# MTX_Tap_an_er_V13_Nopoti_2018_11_30.net
KiCad netlist of a schematic drawn in EAGLE
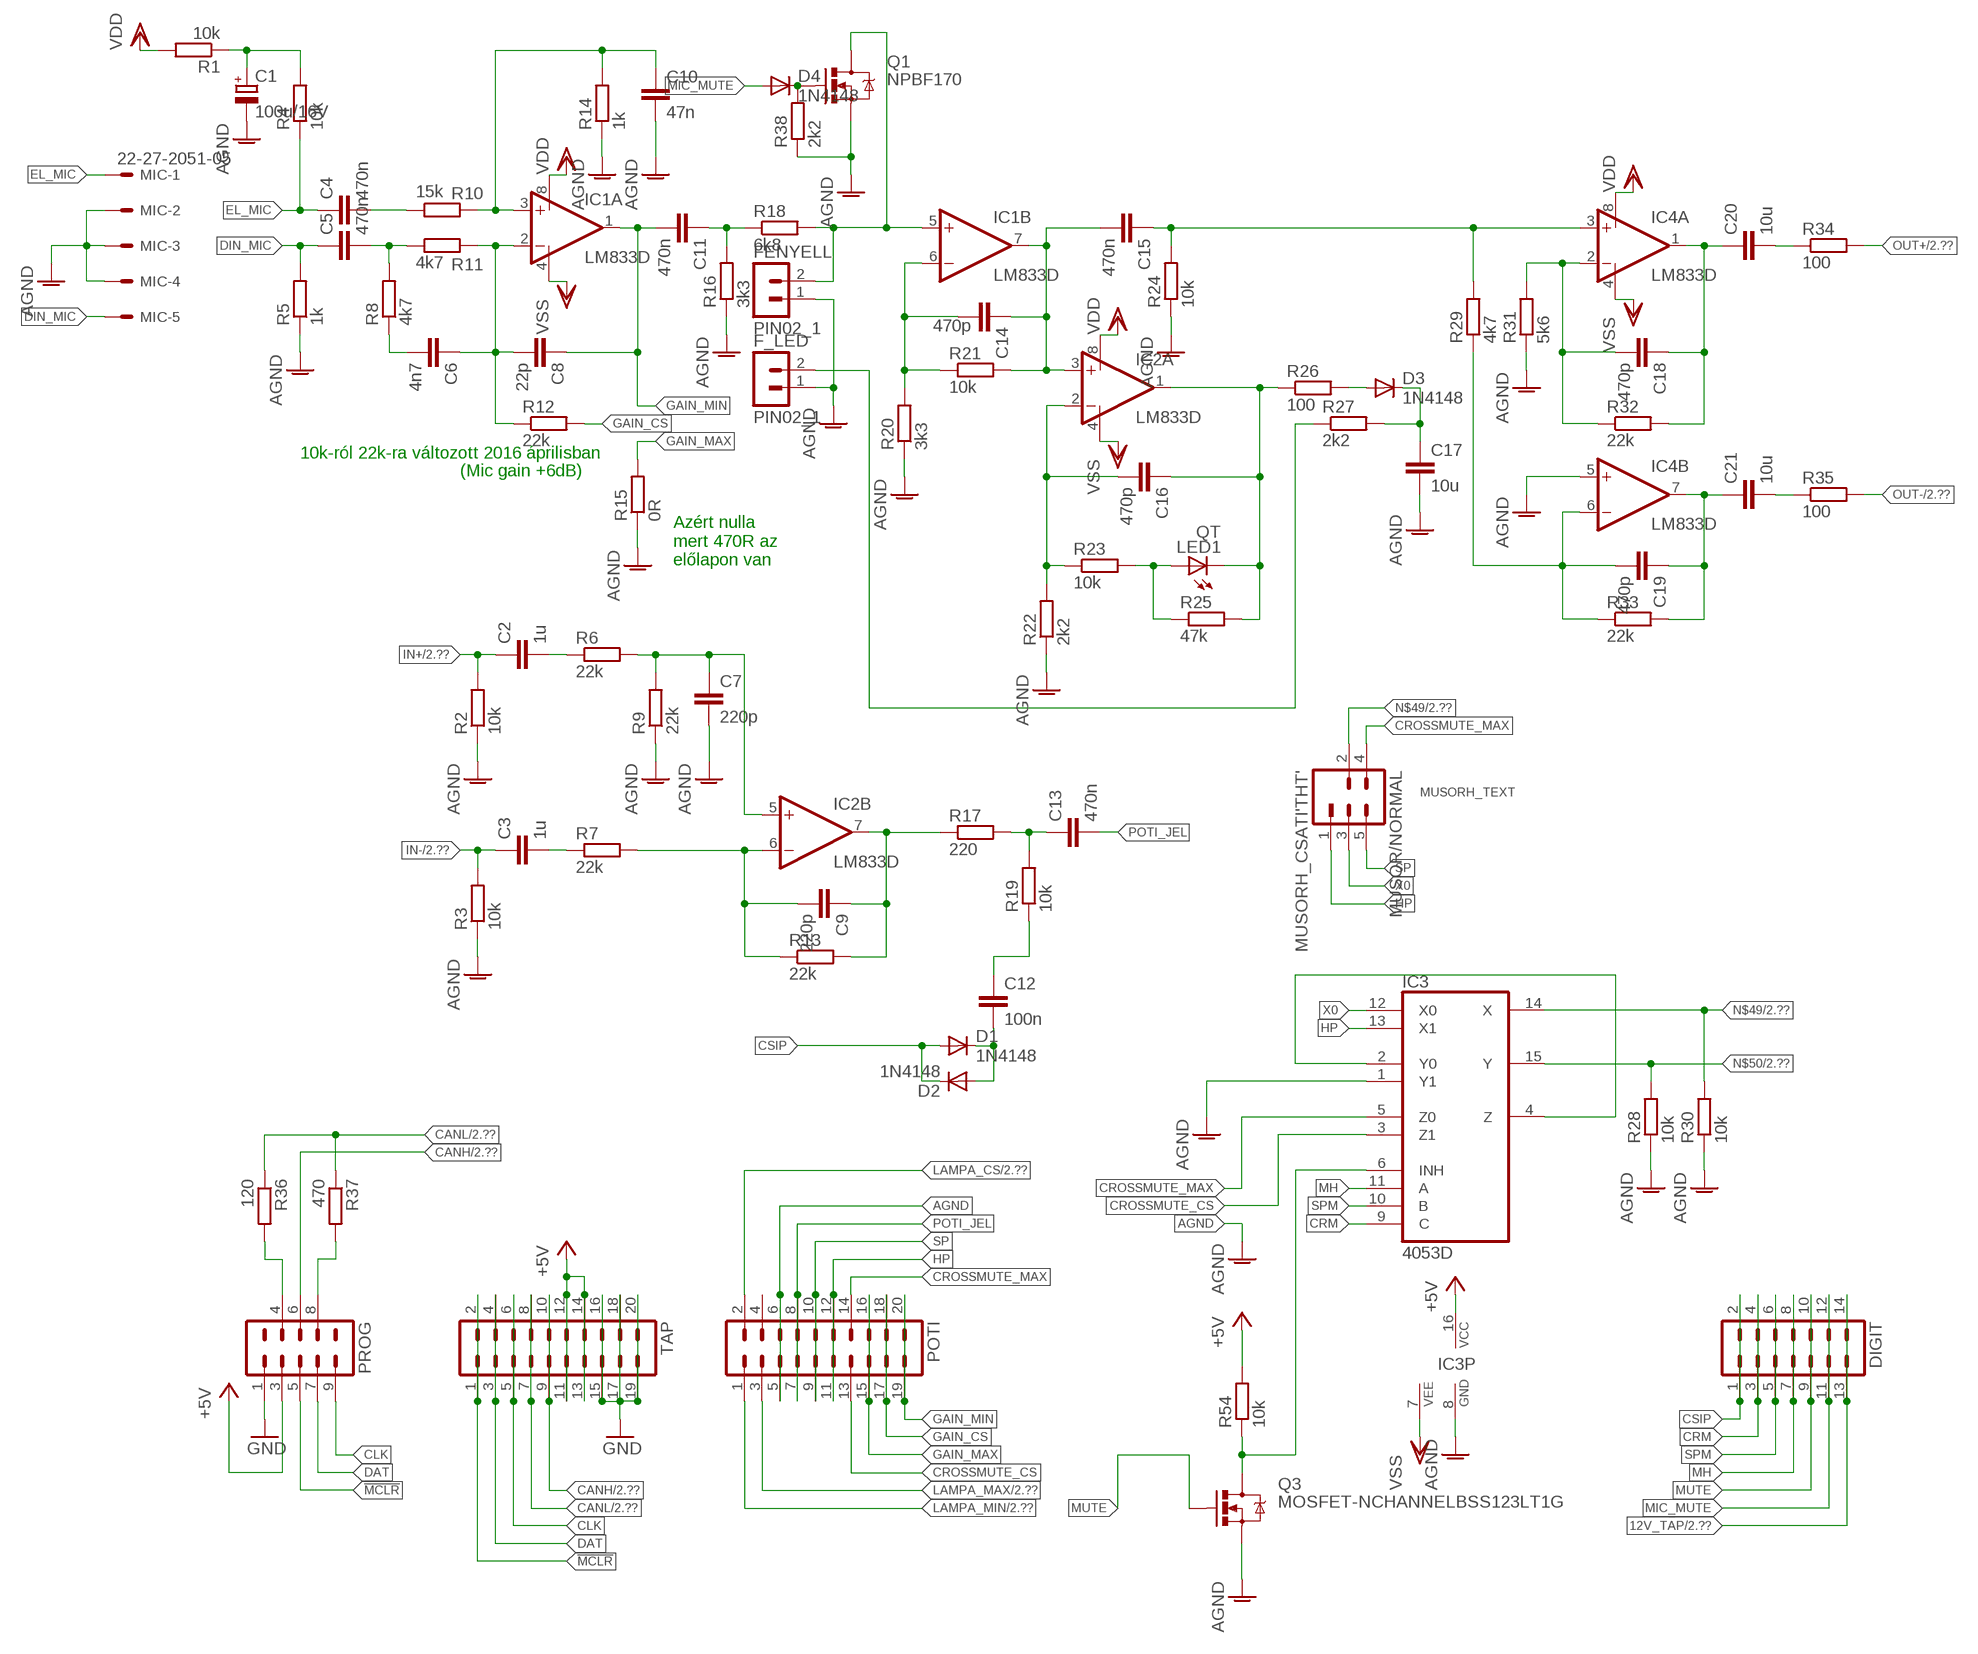
[diagram p0: schematic, sheet 1]
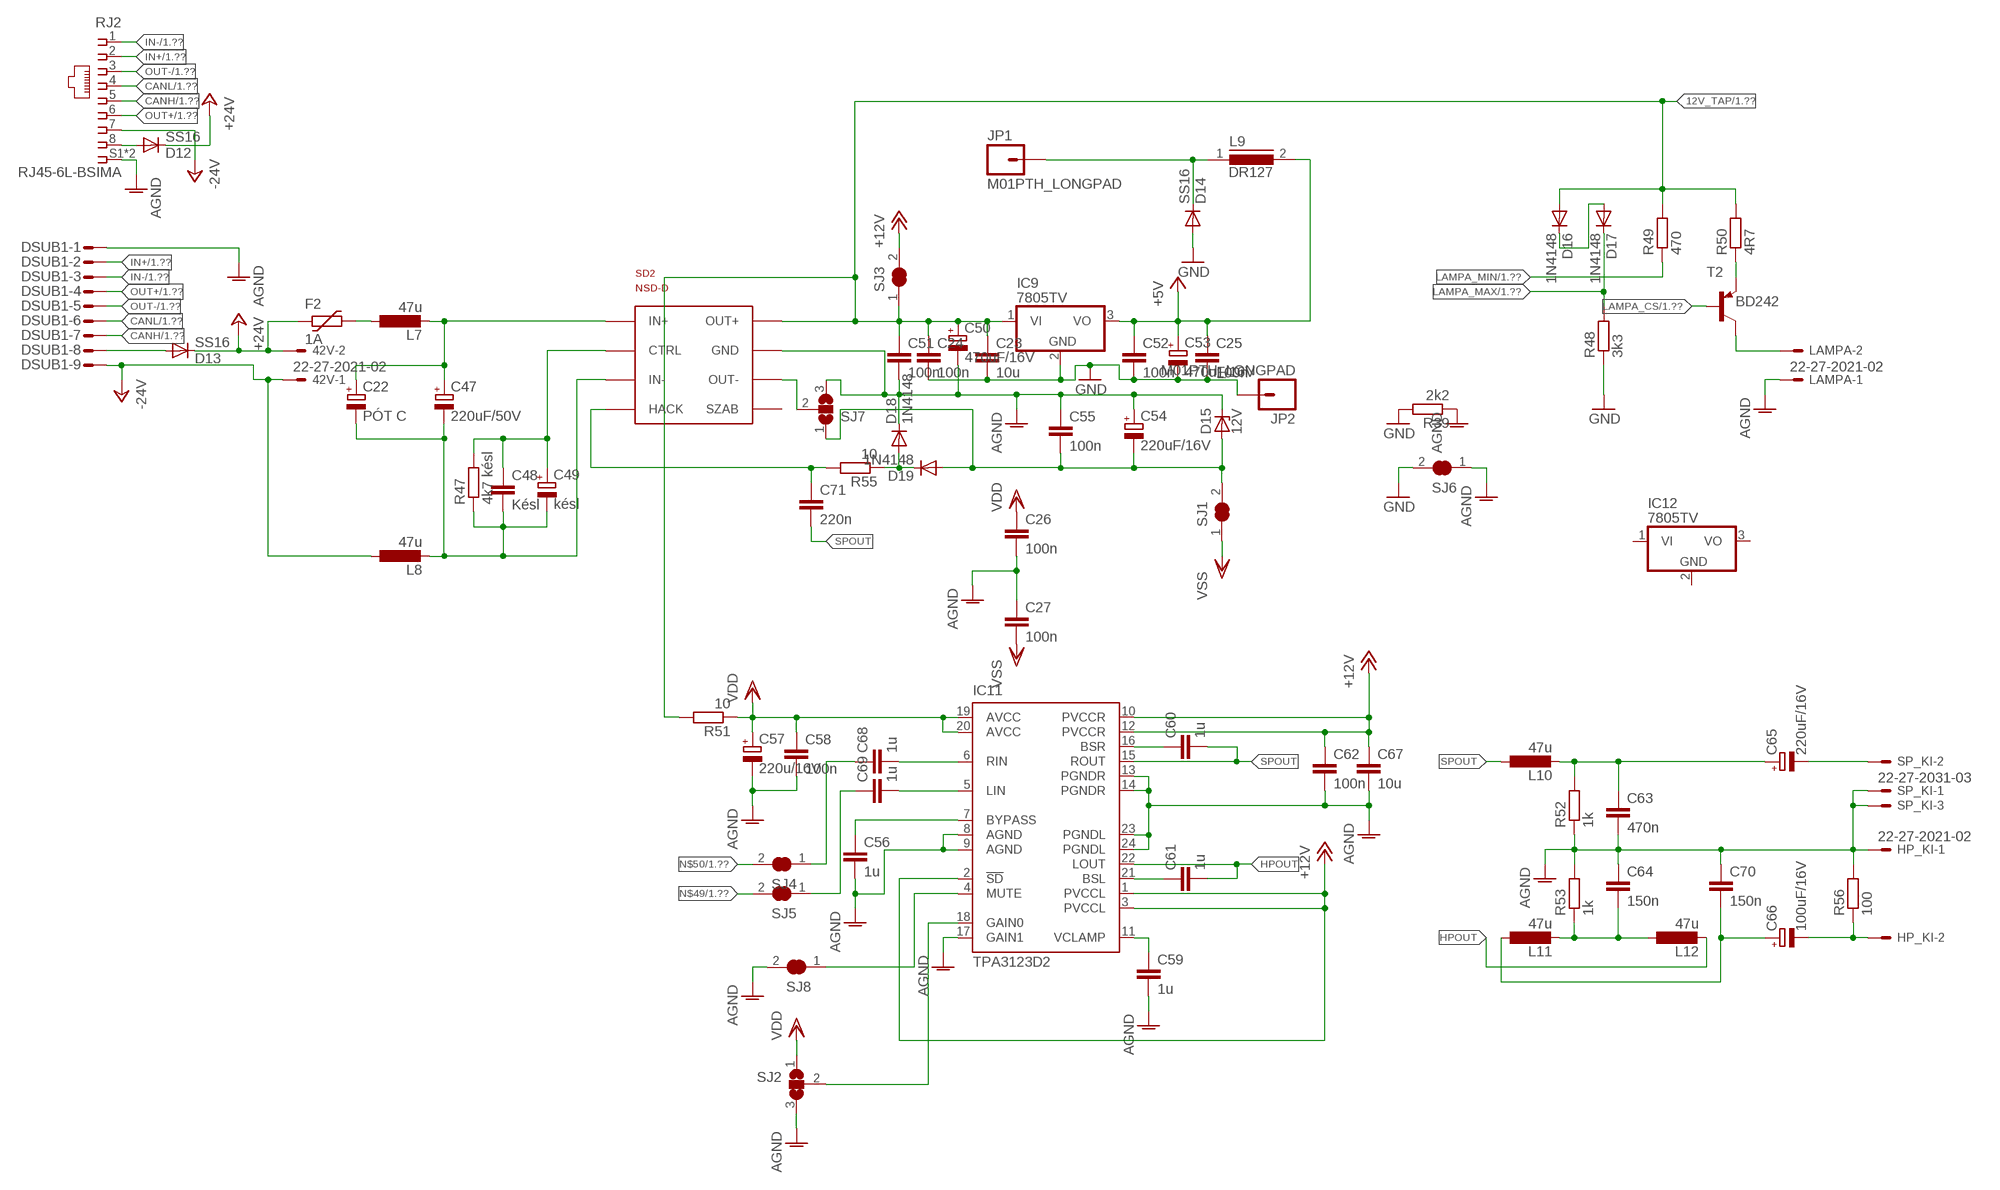
[diagram p1: schematic, sheet 2]

(export (version "E")
  (design (tool "Eeschema 10.0.6"))
  (components
    (comp (ref "42V")
      (value "22-27-2021-02")
      (footprint "eagle-import:6410-02")
      (libsource (lib "eagle-import") (part "22-?-0227-2021"))
    )
    (comp (ref "C22")
      (value "PÓT C")
      (footprint "eagle-import:E3,5-8")
      (libsource (lib "eagle-import") (part "CPOL-EUE3.5-8"))
    )
    (comp (ref "C23")
      (value "10u")
      (footprint "eagle-import:C0805")
      (libsource (lib "eagle-import") (part "C-EUC0805"))
    )
    (comp (ref "C24")
      (value "100n")
      (footprint "eagle-import:C0805")
      (libsource (lib "eagle-import") (part "C-EUC0805"))
    )
    (comp (ref "C25")
      (value "100n")
      (footprint "eagle-import:C0805")
      (libsource (lib "eagle-import") (part "C-EUC0805"))
    )
    (comp (ref "C26")
      (value "100n")
      (footprint "eagle-import:C0805")
      (libsource (lib "eagle-import") (part "C-EUC0805"))
    )
    (comp (ref "C27")
      (value "100n")
      (footprint "eagle-import:C0805")
      (libsource (lib "eagle-import") (part "C-EUC0805"))
    )
    (comp (ref "C47")
      (value "220uF/50V")
      (footprint "eagle-import:E3,5-8")
      (libsource (lib "eagle-import") (part "CPOL-EUE3.5-8"))
    )
    (comp (ref "C48")
      (value "Késl")
      (footprint "eagle-import:C0805")
      (libsource (lib "eagle-import") (part "C-EUC0805"))
    )
    (comp (ref "C49")
      (value "késl")
      (footprint "eagle-import:E2,5-5")
      (libsource (lib "eagle-import") (part "CPOL-EUE2.5-5"))
    )
    (comp (ref "C50")
      (value "470uF/16V")
      (footprint "eagle-import:E3,5-8")
      (libsource (lib "eagle-import") (part "CPOL-EUE3.5-8"))
    )
    (comp (ref "C51")
      (value "100n")
      (footprint "eagle-import:C0805")
      (libsource (lib "eagle-import") (part "C-EUC0805"))
    )
    (comp (ref "C52")
      (value "100n")
      (footprint "eagle-import:C0805")
      (libsource (lib "eagle-import") (part "C-EUC0805"))
    )
    (comp (ref "C53")
      (value "470uF/16V")
      (footprint "eagle-import:E3,5-8")
      (libsource (lib "eagle-import") (part "CPOL-EUE3.5-8"))
    )
    (comp (ref "C54")
      (value "220uF/16V")
      (footprint "eagle-import:E2,5-7")
      (libsource (lib "eagle-import") (part "CPOL-EUE2.5-7"))
    )
    (comp (ref "C55")
      (value "100n")
      (footprint "eagle-import:C0805")
      (libsource (lib "eagle-import") (part "C-EUC0805"))
    )
    (comp (ref "C56")
      (value "1u")
      (footprint "eagle-import:C0805")
      (libsource (lib "eagle-import") (part "C-EUC0805"))
    )
    (comp (ref "C57")
      (value "220u/16V")
      (footprint "eagle-import:E2,5-7")
      (libsource (lib "eagle-import") (part "CPOL-EUE2.5-7"))
    )
    (comp (ref "C58")
      (value "100n")
      (footprint "eagle-import:C0805")
      (libsource (lib "eagle-import") (part "C-EUC0805"))
    )
    (comp (ref "C59")
      (value "1u")
      (footprint "eagle-import:C0805")
      (libsource (lib "eagle-import") (part "C-EUC0805"))
    )
    (comp (ref "C60")
      (value "1u")
      (footprint "eagle-import:C0805")
      (libsource (lib "eagle-import") (part "C-EUC0805"))
    )
    (comp (ref "C61")
      (value "1u")
      (footprint "eagle-import:C0805")
      (libsource (lib "eagle-import") (part "C-EUC0805"))
    )
    (comp (ref "C62")
      (value "100n")
      (footprint "eagle-import:C0805")
      (libsource (lib "eagle-import") (part "C-EUC0805"))
    )
    (comp (ref "C63")
      (value "470n")
      (footprint "eagle-import:C0805")
      (libsource (lib "eagle-import") (part "C-EUC0805"))
    )
    (comp (ref "C64")
      (value "150n")
      (footprint "eagle-import:C0805")
      (libsource (lib "eagle-import") (part "C-EUC0805"))
    )
    (comp (ref "C65")
      (value "220uF/16V")
      (footprint "eagle-import:E2,5-7")
      (libsource (lib "eagle-import") (part "CPOL-EUE2.5-7"))
    )
    (comp (ref "C66")
      (value "100uF/16V")
      (footprint "eagle-import:E2,5-6")
      (libsource (lib "eagle-import") (part "CPOL-EUE2.5-6"))
    )
    (comp (ref "C67")
      (value "10u")
      (footprint "eagle-import:C0805")
      (libsource (lib "eagle-import") (part "C-EUC0805"))
    )
    (comp (ref "C68")
      (value "1u")
      (footprint "eagle-import:C0805")
      (libsource (lib "eagle-import") (part "C-EUC0805"))
    )
    (comp (ref "C69")
      (value "1u")
      (footprint "eagle-import:C0805")
      (libsource (lib "eagle-import") (part "C-EUC0805"))
    )
    (comp (ref "C70")
      (value "150n")
      (footprint "eagle-import:C0805")
      (libsource (lib "eagle-import") (part "C-EUC0805"))
    )
    (comp (ref "C71")
      (value "220n")
      (footprint "eagle-import:C0805")
      (libsource (lib "eagle-import") (part "C-EUC0805"))
    )
    (comp (ref "D12")
      (value "SS16")
      (footprint "eagle-import:DO-214AC")
      (libsource (lib "eagle-import") (part "dp_devices_DIODE-DO-214AC"))
    )
    (comp (ref "D13")
      (value "SS16")
      (footprint "eagle-import:DO-214AC")
      (libsource (lib "eagle-import") (part "dp_devices_DIODE-DO-214AC"))
    )
    (comp (ref "D14")
      (value "SS16")
      (footprint "eagle-import:DO-214AC")
      (libsource (lib "eagle-import") (part "dp_devices_DIODE-DO-214AC"))
    )
    (comp (ref "D15")
      (value "12V")
      (footprint "eagle-import:SOD80C")
      (libsource (lib "eagle-import") (part "ZENER-DIODESOD80C"))
    )
    (comp (ref "D16")
      (value "1N4148")
      (footprint "eagle-import:SOD80C")
      (libsource (lib "eagle-import") (part "DIODE-SOD80C"))
    )
    (comp (ref "D17")
      (value "1N4148")
      (footprint "eagle-import:SOD80C")
      (libsource (lib "eagle-import") (part "DIODE-SOD80C"))
    )
    (comp (ref "D18")
      (value "1N4148")
      (footprint "eagle-import:SOD80C")
      (libsource (lib "eagle-import") (part "DIODE-SOD80C"))
    )
    (comp (ref "D19")
      (value "1N4148")
      (footprint "eagle-import:SOD80C")
      (libsource (lib "eagle-import") (part "DIODE-SOD80C"))
    )
    (comp (ref "DSUB1")
      (value "M09-182S")
      (footprint "eagle-import:182-009-MALE")
      (libsource (lib "eagle-import") (part "M09?S-182"))
    )
    (comp (ref "F2")
      (value "1A")
      (footprint "eagle-import:PTC1812L")
      (libsource (lib "eagle-import") (part "FUSE_PTC-1812"))
    )
    (comp (ref "HP_KI")
      (value "22-27-2021-02")
      (footprint "eagle-import:6410-02")
      (libsource (lib "eagle-import") (part "22-?-0227-2021"))
    )
    (comp (ref "IC9")
      (value "7805TV")
      (footprint "eagle-import:TO220V")
      (libsource (lib "eagle-import") (part "78TV05"))
    )
    (comp (ref "IC11")
      (value "TPA3123D2")
      (footprint "eagle-import:PWP-TSSOP24")
      (fields (field (name "MPN") "TPA3123D2PWP"))
      (libsource (lib "eagle-import") (part "TPA3123D2"))
    )
    (comp (ref "IC12")
      (value "7805TV")
      (footprint "eagle-import:TO220V")
      (libsource (lib "eagle-import") (part "78TV05"))
    )
    (comp (ref "JP1")
      (value "M01PTH_LONGPAD")
      (footprint "eagle-import:1X01_LONGPAD")
      (libsource (lib "eagle-import") (part "M01PTH_LONGPAD"))
    )
    (comp (ref "JP2")
      (value "M01PTH_LONGPAD")
      (footprint "eagle-import:1X01_LONGPAD")
      (libsource (lib "eagle-import") (part "M01PTH_LONGPAD"))
    )
    (comp (ref "L7")
      (value "47u")
      (footprint "eagle-import:PIS2816")
      (libsource (lib "eagle-import") (part "L-EUPIS2816"))
    )
    (comp (ref "L8")
      (value "47u")
      (footprint "eagle-import:PIS2816")
      (libsource (lib "eagle-import") (part "L-EUPIS2816"))
    )
    (comp (ref "L9")
      (value "DR127")
      (footprint "eagle-import:DR127")
      (libsource (lib "eagle-import") (part "DR127"))
    )
    (comp (ref "L10")
      (value "47u")
      (footprint "eagle-import:PIS2816")
      (libsource (lib "eagle-import") (part "L-EUPIS2816"))
    )
    (comp (ref "L11")
      (value "47u")
      (footprint "eagle-import:PIS2816")
      (libsource (lib "eagle-import") (part "L-EUPIS2816"))
    )
    (comp (ref "L12")
      (value "47u")
      (footprint "eagle-import:PIS2816")
      (libsource (lib "eagle-import") (part "L-EUPIS2816"))
    )
    (comp (ref "LAMPA")
      (value "22-27-2021-02")
      (footprint "eagle-import:6410-02")
      (libsource (lib "eagle-import") (part "22-?-0227-2021"))
    )
    (comp (ref "R39")
      (value "2k2")
      (footprint "eagle-import:R0805")
      (libsource (lib "eagle-import") (part "R-EU_R0805"))
    )
    (comp (ref "R47")
      (value "4k7 késl")
      (footprint "eagle-import:R0805")
      (libsource (lib "eagle-import") (part "R-EU_R0805"))
    )
    (comp (ref "R48")
      (value "3k3")
      (footprint "eagle-import:R0805")
      (libsource (lib "eagle-import") (part "R-EU_R0805"))
    )
    (comp (ref "R49")
      (value "470")
      (footprint "eagle-import:R0805")
      (libsource (lib "eagle-import") (part "R-EU_R0805"))
    )
    (comp (ref "R50")
      (value "4R7")
      (footprint "eagle-import:R0805")
      (libsource (lib "eagle-import") (part "R-EU_R0805"))
    )
    (comp (ref "R51")
      (value "10")
      (footprint "eagle-import:R1210")
      (libsource (lib "eagle-import") (part "R-EU_R1210"))
    )
    (comp (ref "R52")
      (value "1k")
      (footprint "eagle-import:R0805")
      (libsource (lib "eagle-import") (part "R-EU_R0805"))
    )
    (comp (ref "R53")
      (value "1k")
      (footprint "eagle-import:R0805")
      (libsource (lib "eagle-import") (part "R-EU_R0805"))
    )
    (comp (ref "R55")
      (value "10")
      (footprint "eagle-import:R0805")
      (libsource (lib "eagle-import") (part "R-EU_R0805"))
    )
    (comp (ref "R56")
      (value "100")
      (footprint "eagle-import:R0805")
      (libsource (lib "eagle-import") (part "R-EU_R0805"))
    )
    (comp (ref "RJ2")
      (value "RJ45-6L-BSIMA")
      (footprint "eagle-import:RJ45")
      (fields (field (name "MPN") "RJ45-6L-B"))
      (libsource (lib "eagle-import") (part "RJ45SIMA-6L-B"))
    )
    (comp (ref "SD2")
      (value "NSD-D")
      (footprint "eagle-import:NSD-D")
      (libsource (lib "eagle-import") (part "NSD-D"))
    )
    (comp (ref "SJ1")
      (value "SOLDERJUMPER_CLOSED")
      (footprint "eagle-import:SOLDERJUMPER_CLOSEDWIRE")
      (libsource (lib "eagle-import") (part "SOLDERJUMPER_CLOSED"))
    )
    (comp (ref "SJ2")
      (value "SJ2WW12")
      (footprint "eagle-import:SJ_2W_12")
      (libsource (lib "eagle-import") (part "SJ2WW12"))
    )
    (comp (ref "SJ3")
      (value "SOLDERJUMPER_CLOSED")
      (footprint "eagle-import:SOLDERJUMPER_CLOSEDWIRE")
      (libsource (lib "eagle-import") (part "SOLDERJUMPER_CLOSED"))
    )
    (comp (ref "SJ4")
      (value "SOLDERJUMPER_CLOSED")
      (footprint "eagle-import:SOLDERJUMPER_CLOSEDWIRE")
      (libsource (lib "eagle-import") (part "SOLDERJUMPER_CLOSED"))
    )
    (comp (ref "SJ5")
      (value "SOLDERJUMPER_CLOSED")
      (footprint "eagle-import:SOLDERJUMPER_CLOSEDWIRE")
      (libsource (lib "eagle-import") (part "SOLDERJUMPER_CLOSED"))
    )
    (comp (ref "SJ6")
      (value "SOLDERJUMPER_CLOSED")
      (footprint "eagle-import:SOLDERJUMPER_CLOSEDWIRE")
      (libsource (lib "eagle-import") (part "SOLDERJUMPER_CLOSED"))
    )
    (comp (ref "SJ7")
      (value "SJ2WW23")
      (footprint "eagle-import:SJ_2W_23")
      (libsource (lib "eagle-import") (part "SJ2WW23"))
    )
    (comp (ref "SJ8")
      (value "SOLDERJUMPER_CLOSED")
      (footprint "eagle-import:SOLDERJUMPER_CLOSEDWIRE")
      (libsource (lib "eagle-import") (part "SOLDERJUMPER_CLOSED"))
    )
    (comp (ref "SP_KI")
      (value "22-27-2031-03")
      (footprint "eagle-import:6410-03")
      (libsource (lib "eagle-import") (part "22-?-0327-2031"))
    )
    (comp (ref "T2")
      (value "BD242")
      (footprint "eagle-import:TO220V")
      (libsource (lib "eagle-import") (part "-PNP-TO220V"))
    )
    (comp (ref "C1")
      (value "100u/16V")
      (footprint "eagle-import:E2,5-5")
      (libsource (lib "eagle-import") (part "CPOL-EUE2.5-5"))
    )
    (comp (ref "C2")
      (value "1u")
      (footprint "eagle-import:C0805")
      (libsource (lib "eagle-import") (part "C-EUC0805"))
    )
    (comp (ref "C3")
      (value "1u")
      (footprint "eagle-import:C0805")
      (libsource (lib "eagle-import") (part "C-EUC0805"))
    )
    (comp (ref "C4")
      (value "470n")
      (footprint "eagle-import:C0805")
      (libsource (lib "eagle-import") (part "C-EUC0805"))
    )
    (comp (ref "C5")
      (value "470n")
      (footprint "eagle-import:C0805")
      (libsource (lib "eagle-import") (part "C-EUC0805"))
    )
    (comp (ref "C6")
      (value "4n7")
      (footprint "eagle-import:C0805")
      (libsource (lib "eagle-import") (part "C-EUC0805"))
    )
    (comp (ref "C7")
      (value "220p")
      (footprint "eagle-import:C0805")
      (libsource (lib "eagle-import") (part "C-EUC0805"))
    )
    (comp (ref "C8")
      (value "22p")
      (footprint "eagle-import:C0805")
      (libsource (lib "eagle-import") (part "C-EUC0805"))
    )
    (comp (ref "C9")
      (value "220p")
      (footprint "eagle-import:C0805")
      (libsource (lib "eagle-import") (part "C-EUC0805"))
    )
    (comp (ref "C10")
      (value "47n")
      (footprint "eagle-import:C0805")
      (libsource (lib "eagle-import") (part "C-EUC0805"))
    )
    (comp (ref "C11")
      (value "470n")
      (footprint "eagle-import:C0805")
      (libsource (lib "eagle-import") (part "C-EUC0805"))
    )
    (comp (ref "C12")
      (value "100n")
      (footprint "eagle-import:C0805")
      (libsource (lib "eagle-import") (part "C-EUC0805"))
    )
    (comp (ref "C13")
      (value "470n")
      (footprint "eagle-import:C0805")
      (libsource (lib "eagle-import") (part "C-EUC0805"))
    )
    (comp (ref "C14")
      (value "470p")
      (footprint "eagle-import:C0805")
      (libsource (lib "eagle-import") (part "C-EUC0805"))
    )
    (comp (ref "C15")
      (value "470n")
      (footprint "eagle-import:C0805")
      (libsource (lib "eagle-import") (part "C-EUC0805"))
    )
    (comp (ref "C16")
      (value "470p")
      (footprint "eagle-import:C0805")
      (libsource (lib "eagle-import") (part "C-EUC0805"))
    )
    (comp (ref "C17")
      (value "10u")
      (footprint "eagle-import:C0805")
      (libsource (lib "eagle-import") (part "C-EUC0805"))
    )
    (comp (ref "C18")
      (value "470p")
      (footprint "eagle-import:C0805")
      (libsource (lib "eagle-import") (part "C-EUC0805"))
    )
    (comp (ref "C19")
      (value "470p")
      (footprint "eagle-import:C0805")
      (libsource (lib "eagle-import") (part "C-EUC0805"))
    )
    (comp (ref "C20")
      (value "10u")
      (footprint "eagle-import:C0805")
      (libsource (lib "eagle-import") (part "C-EUC0805"))
    )
    (comp (ref "C21")
      (value "10u")
      (footprint "eagle-import:C0805")
      (libsource (lib "eagle-import") (part "C-EUC0805"))
    )
    (comp (ref "D1")
      (value "1N4148")
      (footprint "eagle-import:SOD80C")
      (libsource (lib "eagle-import") (part "DIODE-SOD80C"))
    )
    (comp (ref "D2")
      (value "1N4148")
      (footprint "eagle-import:SOD80C")
      (libsource (lib "eagle-import") (part "DIODE-SOD80C"))
    )
    (comp (ref "D3")
      (value "1N4148")
      (footprint "eagle-import:SOD80C")
      (libsource (lib "eagle-import") (part "DIODE-SOD80C"))
    )
    (comp (ref "D4")
      (value "1N4148")
      (footprint "eagle-import:SOD80C")
      (libsource (lib "eagle-import") (part "DIODE-SOD80C"))
    )
    (comp (ref "DIGIT")
      (value "MA07-2")
      (footprint "eagle-import:MA07-2")
      (libsource (lib "eagle-import") (part "MA07-2"))
    )
    (comp (ref "FENYELL")
      (value "PIN02_1")
      (footprint "eagle-import:PIN02_1")
      (libsource (lib "eagle-import") (part "PIN02_1"))
    )
    (comp (ref "F_LED")
      (value "PIN02_1")
      (footprint "eagle-import:PIN02_1")
      (libsource (lib "eagle-import") (part "PIN02_1"))
    )
    (comp (ref "IC1")
      (value "LM833D")
      (footprint "eagle-import:SO08")
      (libsource (lib "eagle-import") (part "LM833D"))
    )
    (comp (ref "IC2")
      (value "LM833D")
      (footprint "eagle-import:SO08")
      (libsource (lib "eagle-import") (part "LM833D"))
    )
    (comp (ref "IC3")
      (value "4053D")
      (footprint "eagle-import:SO16")
      (libsource (lib "eagle-import") (part "4053D"))
    )
    (comp (ref "IC4")
      (value "LM833D")
      (footprint "eagle-import:SO08")
      (libsource (lib "eagle-import") (part "LM833D"))
    )
    (comp (ref "LED1")
      (value "QT")
      (footprint "eagle-import:LED3MM")
      (libsource (lib "eagle-import") (part "LED3MM"))
    )
    (comp (ref "MIC")
      (value "22-27-2051-05")
      (footprint "eagle-import:6410-05")
      (libsource (lib "eagle-import") (part "22-?-0527-2051"))
    )
    (comp (ref "MUSOR/NORMAL")
      (value "MUSORH_CSATI'THT'")
      (footprint "eagle-import:MUSORH_CSATI")
      (libsource (lib "eagle-import") (part "MUSORH_CSATI'THT'"))
    )
    (comp (ref "POTI")
      (value "MA10-2")
      (footprint "eagle-import:MA10-2")
      (libsource (lib "eagle-import") (part "MA10-2"))
    )
    (comp (ref "PROG")
      (value "CN_CANTAN")
      (footprint "eagle-import:CN_CANTAN")
      (libsource (lib "eagle-import") (part "CN_CANTAN"))
    )
    (comp (ref "Q1")
      (value "NPBF170")
      (footprint "eagle-import:SOT23")
      (libsource (lib "eagle-import") (part "MOSFET-NCHANNELBSS138"))
    )
    (comp (ref "Q3")
      (value "MOSFET-NCHANNELBSS123LT1G")
      (footprint "eagle-import:SOT23")
      (libsource (lib "eagle-import") (part "MOSFET-NCHANNELBSS123LT1G"))
    )
    (comp (ref "R1")
      (value "10k")
      (footprint "eagle-import:R0805")
      (libsource (lib "eagle-import") (part "R-EU_R0805"))
    )
    (comp (ref "R2")
      (value "10k")
      (footprint "eagle-import:R0805")
      (libsource (lib "eagle-import") (part "R-EU_R0805"))
    )
    (comp (ref "R3")
      (value "10k")
      (footprint "eagle-import:R0805")
      (libsource (lib "eagle-import") (part "R-EU_R0805"))
    )
    (comp (ref "R4")
      (value "10k")
      (footprint "eagle-import:R0805")
      (libsource (lib "eagle-import") (part "R-EU_R0805"))
    )
    (comp (ref "R5")
      (value "1k")
      (footprint "eagle-import:R0805")
      (libsource (lib "eagle-import") (part "R-EU_R0805"))
    )
    (comp (ref "R6")
      (value "22k")
      (footprint "eagle-import:R0805")
      (libsource (lib "eagle-import") (part "R-EU_R0805"))
    )
    (comp (ref "R7")
      (value "22k")
      (footprint "eagle-import:R0805")
      (libsource (lib "eagle-import") (part "R-EU_R0805"))
    )
    (comp (ref "R8")
      (value "4k7")
      (footprint "eagle-import:R0805")
      (libsource (lib "eagle-import") (part "R-EU_R0805"))
    )
    (comp (ref "R9")
      (value "22k")
      (footprint "eagle-import:R0805")
      (libsource (lib "eagle-import") (part "R-EU_R0805"))
    )
    (comp (ref "R10")
      (value "15k")
      (footprint "eagle-import:R0805")
      (libsource (lib "eagle-import") (part "R-EU_R0805"))
    )
    (comp (ref "R11")
      (value "4k7")
      (footprint "eagle-import:R0805")
      (libsource (lib "eagle-import") (part "R-EU_R0805"))
    )
    (comp (ref "R12")
      (value "22k")
      (footprint "eagle-import:R0805")
      (libsource (lib "eagle-import") (part "R-EU_R0805"))
    )
    (comp (ref "R13")
      (value "22k")
      (footprint "eagle-import:R0805")
      (libsource (lib "eagle-import") (part "R-EU_R0805"))
    )
    (comp (ref "R14")
      (value "1k")
      (footprint "eagle-import:R0805")
      (libsource (lib "eagle-import") (part "R-EU_R0805"))
    )
    (comp (ref "R15")
      (value "0R")
      (footprint "eagle-import:R0805")
      (libsource (lib "eagle-import") (part "R-EU_R0805"))
    )
    (comp (ref "R16")
      (value "3k3")
      (footprint "eagle-import:R0805")
      (libsource (lib "eagle-import") (part "R-EU_R0805"))
    )
    (comp (ref "R17")
      (value "220")
      (footprint "eagle-import:R0805")
      (libsource (lib "eagle-import") (part "R-EU_R0805"))
    )
    (comp (ref "R18")
      (value "6k8")
      (footprint "eagle-import:R0805")
      (libsource (lib "eagle-import") (part "R-EU_R0805"))
    )
    (comp (ref "R19")
      (value "10k")
      (footprint "eagle-import:R0805")
      (libsource (lib "eagle-import") (part "R-EU_R0805"))
    )
    (comp (ref "R20")
      (value "3k3")
      (footprint "eagle-import:R0805")
      (libsource (lib "eagle-import") (part "R-EU_R0805"))
    )
    (comp (ref "R21")
      (value "10k")
      (footprint "eagle-import:R0805")
      (libsource (lib "eagle-import") (part "R-EU_R0805"))
    )
    (comp (ref "R22")
      (value "2k2")
      (footprint "eagle-import:R0805")
      (libsource (lib "eagle-import") (part "R-EU_R0805"))
    )
    (comp (ref "R23")
      (value "10k")
      (footprint "eagle-import:R0805")
      (libsource (lib "eagle-import") (part "R-EU_R0805"))
    )
    (comp (ref "R24")
      (value "10k")
      (footprint "eagle-import:R0805")
      (libsource (lib "eagle-import") (part "R-EU_R0805"))
    )
    (comp (ref "R25")
      (value "47k")
      (footprint "eagle-import:R0805")
      (libsource (lib "eagle-import") (part "R-EU_R0805"))
    )
    (comp (ref "R26")
      (value "100")
      (footprint "eagle-import:R0805")
      (libsource (lib "eagle-import") (part "R-EU_R0805"))
    )
    (comp (ref "R27")
      (value "2k2")
      (footprint "eagle-import:R0805")
      (libsource (lib "eagle-import") (part "R-EU_R0805"))
    )
    (comp (ref "R28")
      (value "10k")
      (footprint "eagle-import:R0805")
      (libsource (lib "eagle-import") (part "R-EU_R0805"))
    )
    (comp (ref "R29")
      (value "4k7")
      (footprint "eagle-import:R0805")
      (libsource (lib "eagle-import") (part "R-EU_R0805"))
    )
    (comp (ref "R30")
      (value "10k")
      (footprint "eagle-import:R0805")
      (libsource (lib "eagle-import") (part "R-EU_R0805"))
    )
    (comp (ref "R31")
      (value "5k6")
      (footprint "eagle-import:R0805")
      (libsource (lib "eagle-import") (part "R-EU_R0805"))
    )
    (comp (ref "R32")
      (value "22k")
      (footprint "eagle-import:R0805")
      (libsource (lib "eagle-import") (part "R-EU_R0805"))
    )
    (comp (ref "R33")
      (value "22k")
      (footprint "eagle-import:R0805")
      (libsource (lib "eagle-import") (part "R-EU_R0805"))
    )
    (comp (ref "R34")
      (value "100")
      (footprint "eagle-import:R0805")
      (libsource (lib "eagle-import") (part "R-EU_R0805"))
    )
    (comp (ref "R35")
      (value "100")
      (footprint "eagle-import:R0805")
      (libsource (lib "eagle-import") (part "R-EU_R0805"))
    )
    (comp (ref "R36")
      (value "120")
      (footprint "eagle-import:R0805")
      (libsource (lib "eagle-import") (part "R-EU_R0805"))
    )
    (comp (ref "R37")
      (value "470")
      (footprint "eagle-import:R0805")
      (libsource (lib "eagle-import") (part "R-EU_R0805"))
    )
    (comp (ref "R38")
      (value "2k2")
      (footprint "eagle-import:R0805")
      (libsource (lib "eagle-import") (part "R-EU_R0805"))
    )
    (comp (ref "R54")
      (value "10k")
      (footprint "eagle-import:R0805")
      (libsource (lib "eagle-import") (part "R-EU_R0805"))
    )
    (comp (ref "TAP")
      (value "MA10-2")
      (footprint "eagle-import:MA10-2")
      (libsource (lib "eagle-import") (part "MA10-2"))
    )
    (comp (ref "U$1")
      (value "MUSORH_TEXT")
      (footprint "eagle-import:MUSORH_TEXT")
      (libsource (lib "eagle-import") (part "MUSORH_TEXT"))
    )
  )
  (nets
    (net (code "1") (name "+5V") (class "Default")
      (node (ref "C25") (pin "1") (pinfunction "1_1") (pintype "passive"))
      (node (ref "C52") (pin "1") (pinfunction "1_1") (pintype "passive"))
      (node (ref "C53") (pin "+") (pinfunction "+_+") (pintype "passive"))
      (node (ref "IC3") (pin "16") (pinfunction "VCC_16") (pintype "power_in"))
      (node (ref "IC9") (pin "3") (pinfunction "VO_3") (pintype "passive"))
      (node (ref "L9") (pin "2") (pinfunction "2_2") (pintype "passive"))
      (node (ref "PROG") (pin "3") (pinfunction "3_3") (pintype "passive"))
      (node (ref "R54") (pin "2") (pinfunction "2_2") (pintype "passive"))
      (node (ref "TAP") (pin "11") (pinfunction "11_11") (pintype "passive"))
      (node (ref "TAP") (pin "12") (pinfunction "12_12") (pintype "passive"))
      (node (ref "TAP") (pin "13") (pinfunction "13_13") (pintype "passive"))
      (node (ref "TAP") (pin "14") (pinfunction "14_14") (pintype "passive"))
    )
    (net (code "2") (name "+12V") (class "Default")
      (node (ref "C62") (pin "1") (pinfunction "1_1") (pintype "passive"))
      (node (ref "C67") (pin "1") (pinfunction "1_1") (pintype "passive"))
      (node (ref "IC11") (pin "1") (pinfunction "PVCCL_1") (pintype "input"))
      (node (ref "IC11") (pin "10") (pinfunction "PVCCR_10") (pintype "input"))
      (node (ref "IC11") (pin "12") (pinfunction "PVCCR_12") (pintype "input"))
      (node (ref "IC11") (pin "2") (pinfunction "~{SD}_2") (pintype "input"))
      (node (ref "IC11") (pin "3") (pinfunction "PVCCL_3") (pintype "input"))
      (node (ref "SJ3") (pin "2") (pinfunction "2_2") (pintype "passive"))
    )
    (net (code "3") (name "+24V") (class "Default")
      (node (ref "42V") (pin "2") (pinfunction "S_2") (pintype "passive"))
      (node (ref "D12") (pin "1") (pinfunction "C_1") (pintype "passive"))
      (node (ref "D13") (pin "1") (pinfunction "C_1") (pintype "passive"))
      (node (ref "F2") (pin "1") (pinfunction "1_1") (pintype "passive"))
    )
    (net (code "4") (name "-24V") (class "Default")
      (node (ref "42V") (pin "1") (pinfunction "S_1") (pintype "passive"))
      (node (ref "DSUB1") (pin "9") (pinfunction "M_9") (pintype "passive"))
      (node (ref "L8") (pin "1") (pinfunction "1_1") (pintype "passive"))
      (node (ref "RJ2") (pin "7") (pinfunction "7_7") (pintype "passive"))
    )
    (net (code "5") (name "12V_TAP") (class "Default")
      (node (ref "C23") (pin "1") (pinfunction "1_1") (pintype "passive"))
      (node (ref "C24") (pin "1") (pinfunction "1_1") (pintype "passive"))
      (node (ref "C50") (pin "+") (pinfunction "+_+") (pintype "passive"))
      (node (ref "C51") (pin "1") (pinfunction "1_1") (pintype "passive"))
      (node (ref "D16") (pin "A") (pinfunction "A_A") (pintype "passive"))
      (node (ref "DIGIT") (pin "13") (pinfunction "13_13") (pintype "passive"))
      (node (ref "DIGIT") (pin "14") (pinfunction "14_14") (pintype "passive"))
      (node (ref "IC9") (pin "1") (pinfunction "VI_1") (pintype "input"))
      (node (ref "R49") (pin "2") (pinfunction "2_2") (pintype "passive"))
      (node (ref "R50") (pin "2") (pinfunction "2_2") (pintype "passive"))
      (node (ref "R51") (pin "2") (pinfunction "2_2") (pintype "passive"))
      (node (ref "SD2") (pin "OUT+") (pinfunction "OUT+_OUT+") (pintype "bidirectional"))
      (node (ref "SJ3") (pin "1") (pinfunction "1_1") (pintype "passive"))
    )
    (net (code "6") (name "AGND") (class "Default")
      (node (ref "C1") (pin "-") (pinfunction "-_-") (pintype "passive"))
      (node (ref "C10") (pin "2") (pinfunction "2_2") (pintype "passive"))
      (node (ref "C17") (pin "2") (pinfunction "2_2") (pintype "passive"))
      (node (ref "C26") (pin "2") (pinfunction "2_2") (pintype "passive"))
      (node (ref "C27") (pin "1") (pinfunction "1_1") (pintype "passive"))
      (node (ref "C50") (pin "-") (pinfunction "-_-") (pintype "passive"))
      (node (ref "C51") (pin "2") (pinfunction "2_2") (pintype "passive"))
      (node (ref "C54") (pin "+") (pinfunction "+_+") (pintype "passive"))
      (node (ref "C55") (pin "1") (pinfunction "1_1") (pintype "passive"))
      (node (ref "C56") (pin "2") (pinfunction "2_2") (pintype "passive"))
      (node (ref "C57") (pin "-") (pinfunction "-_-") (pintype "passive"))
      (node (ref "C58") (pin "2") (pinfunction "2_2") (pintype "passive"))
      (node (ref "C59") (pin "2") (pinfunction "2_2") (pintype "passive"))
      (node (ref "C62") (pin "2") (pinfunction "2_2") (pintype "passive"))
      (node (ref "C63") (pin "2") (pinfunction "2_2") (pintype "passive"))
      (node (ref "C64") (pin "1") (pinfunction "1_1") (pintype "passive"))
      (node (ref "C67") (pin "2") (pinfunction "2_2") (pintype "passive"))
      (node (ref "C7") (pin "2") (pinfunction "2_2") (pintype "passive"))
      (node (ref "C70") (pin "1") (pinfunction "1_1") (pintype "passive"))
      (node (ref "D15") (pin "C") (pinfunction "C_C") (pintype "passive"))
      (node (ref "D18") (pin "C") (pinfunction "C_C") (pintype "passive"))
      (node (ref "DSUB1") (pin "1") (pinfunction "M_1") (pintype "passive"))
      (node (ref "FENYELL") (pin "1") (pinfunction "1_1") (pintype "passive"))
      (node (ref "F_LED") (pin "1") (pinfunction "1_1") (pintype "passive"))
      (node (ref "HP_KI") (pin "1") (pinfunction "S_1") (pintype "passive"))
      (node (ref "IC11") (pin "13") (pinfunction "PGNDR_13") (pintype "input"))
      (node (ref "IC11") (pin "14") (pinfunction "PGNDR_14") (pintype "input"))
      (node (ref "IC11") (pin "17") (pinfunction "GAIN1_17") (pintype "input"))
      (node (ref "IC11") (pin "23") (pinfunction "PGNDL_23") (pintype "input"))
      (node (ref "IC11") (pin "24") (pinfunction "PGNDL_24") (pintype "input"))
      (node (ref "IC11") (pin "8") (pinfunction "AGND_8") (pintype "input"))
      (node (ref "IC11") (pin "9") (pinfunction "AGND_9") (pintype "input"))
      (node (ref "IC3") (pin "1") (pinfunction "Y1_1") (pintype "bidirectional"))
      (node (ref "IC3") (pin "8") (pinfunction "GND_8") (pintype "power_in"))
      (node (ref "IC4") (pin "5") (pinfunction "+IN_5") (pintype "input"))
      (node (ref "LAMPA") (pin "1") (pinfunction "S_1") (pintype "passive"))
      (node (ref "MIC") (pin "2") (pinfunction "S_2") (pintype "passive"))
      (node (ref "MIC") (pin "3") (pinfunction "S_3") (pintype "passive"))
      (node (ref "MIC") (pin "4") (pinfunction "S_4") (pintype "passive"))
      (node (ref "POTI") (pin "5") (pinfunction "5_5") (pintype "passive"))
      (node (ref "POTI") (pin "6") (pinfunction "6_6") (pintype "passive"))
      (node (ref "Q1") (pin "2") (pinfunction "S_2") (pintype "passive"))
      (node (ref "Q3") (pin "2") (pinfunction "S_2") (pintype "passive"))
      (node (ref "R14") (pin "1") (pinfunction "1_1") (pintype "passive"))
      (node (ref "R15") (pin "1") (pinfunction "1_1") (pintype "passive"))
      (node (ref "R16") (pin "1") (pinfunction "1_1") (pintype "passive"))
      (node (ref "R2") (pin "1") (pinfunction "1_1") (pintype "passive"))
      (node (ref "R20") (pin "1") (pinfunction "1_1") (pintype "passive"))
      (node (ref "R22") (pin "1") (pinfunction "1_1") (pintype "passive"))
      (node (ref "R24") (pin "1") (pinfunction "1_1") (pintype "passive"))
      (node (ref "R28") (pin "1") (pinfunction "1_1") (pintype "passive"))
      (node (ref "R3") (pin "1") (pinfunction "1_1") (pintype "passive"))
      (node (ref "R30") (pin "1") (pinfunction "1_1") (pintype "passive"))
      (node (ref "R31") (pin "1") (pinfunction "1_1") (pintype "passive"))
      (node (ref "R38") (pin "1") (pinfunction "1_1") (pintype "passive"))
      (node (ref "R39") (pin "1") (pinfunction "1_1") (pintype "passive"))
      (node (ref "R5") (pin "1") (pinfunction "1_1") (pintype "passive"))
      (node (ref "R52") (pin "1") (pinfunction "1_1") (pintype "passive"))
      (node (ref "R53") (pin "2") (pinfunction "2_2") (pintype "passive"))
      (node (ref "R56") (pin "2") (pinfunction "2_2") (pintype "passive"))
      (node (ref "R9") (pin "1") (pinfunction "1_1") (pintype "passive"))
      (node (ref "RJ2") (pin "S1") (pinfunction "S_S1") (pintype "passive"))
      (node (ref "RJ2") (pin "S2") (pinfunction "S_S2") (pintype "passive"))
      (node (ref "SD2") (pin "COMMON") (pinfunction "GND_COMMON") (pintype "bidirectional"))
      (node (ref "SJ2") (pin "3") (pinfunction "3_3") (pintype "passive"))
      (node (ref "SJ6") (pin "1") (pinfunction "1_1") (pintype "passive"))
      (node (ref "SJ7") (pin "3") (pinfunction "3_3") (pintype "passive"))
      (node (ref "SJ8") (pin "2") (pinfunction "2_2") (pintype "passive"))
      (node (ref "SP_KI") (pin "1") (pinfunction "S_1") (pintype "passive"))
      (node (ref "SP_KI") (pin "3") (pinfunction "S_3") (pintype "passive"))
    )
    (net (code "7") (name "CANH") (class "Default")
      (node (ref "DSUB1") (pin "7") (pinfunction "M_7") (pintype "passive"))
      (node (ref "PROG") (pin "6") (pinfunction "6_6") (pintype "passive"))
      (node (ref "RJ2") (pin "5") (pinfunction "5_5") (pintype "passive"))
      (node (ref "TAP") (pin "10") (pinfunction "10_10") (pintype "passive"))
      (node (ref "TAP") (pin "9") (pinfunction "9_9") (pintype "passive"))
    )
    (net (code "8") (name "CANL") (class "Default")
      (node (ref "DSUB1") (pin "6") (pinfunction "M_6") (pintype "passive"))
      (node (ref "R36") (pin "1") (pinfunction "1_1") (pintype "passive"))
      (node (ref "R37") (pin "1") (pinfunction "1_1") (pintype "passive"))
      (node (ref "RJ2") (pin "4") (pinfunction "4_4") (pintype "passive"))
      (node (ref "TAP") (pin "7") (pinfunction "7_7") (pintype "passive"))
      (node (ref "TAP") (pin "8") (pinfunction "8_8") (pintype "passive"))
    )
    (net (code "9") (name "CLK") (class "Default")
      (node (ref "PROG") (pin "9") (pinfunction "9_9") (pintype "passive"))
      (node (ref "TAP") (pin "5") (pinfunction "5_5") (pintype "passive"))
      (node (ref "TAP") (pin "6") (pinfunction "6_6") (pintype "passive"))
    )
    (net (code "10") (name "CRM") (class "Default")
      (node (ref "DIGIT") (pin "3") (pinfunction "3_3") (pintype "passive"))
      (node (ref "DIGIT") (pin "4") (pinfunction "4_4") (pintype "passive"))
      (node (ref "IC3") (pin "9") (pinfunction "C_9") (pintype "input"))
    )
    (net (code "11") (name "CROSSMUTE_CS") (class "Default")
      (node (ref "IC3") (pin "3") (pinfunction "Z1_3") (pintype "bidirectional"))
      (node (ref "POTI") (pin "13") (pinfunction "13_13") (pintype "passive"))
    )
    (net (code "12") (name "CROSSMUTE_MAX") (class "Default")
      (node (ref "IC3") (pin "5") (pinfunction "Z0_5") (pintype "bidirectional"))
      (node (ref "MUSOR/NORMAL") (pin "4") (pinfunction "4_4") (pintype "passive"))
      (node (ref "POTI") (pin "14") (pinfunction "14_14") (pintype "passive"))
    )
    (net (code "13") (name "CSIP") (class "Default")
      (node (ref "D1") (pin "A") (pinfunction "A_A") (pintype "passive"))
      (node (ref "D2") (pin "C") (pinfunction "C_C") (pintype "passive"))
      (node (ref "DIGIT") (pin "1") (pinfunction "1_1") (pintype "passive"))
      (node (ref "DIGIT") (pin "2") (pinfunction "2_2") (pintype "passive"))
    )
    (net (code "14") (name "DAT") (class "Default")
      (node (ref "PROG") (pin "7") (pinfunction "7_7") (pintype "passive"))
      (node (ref "TAP") (pin "3") (pinfunction "3_3") (pintype "passive"))
      (node (ref "TAP") (pin "4") (pinfunction "4_4") (pintype "passive"))
    )
    (net (code "15") (name "DIN_MIC") (class "Default")
      (node (ref "C5") (pin "1") (pinfunction "1_1") (pintype "passive"))
      (node (ref "MIC") (pin "5") (pinfunction "S_5") (pintype "passive"))
      (node (ref "R5") (pin "2") (pinfunction "2_2") (pintype "passive"))
    )
    (net (code "16") (name "EL_MIC") (class "Default")
      (node (ref "C4") (pin "1") (pinfunction "1_1") (pintype "passive"))
      (node (ref "MIC") (pin "1") (pinfunction "S_1") (pintype "passive"))
      (node (ref "R4") (pin "1") (pinfunction "1_1") (pintype "passive"))
    )
    (net (code "17") (name "GAIN_CS") (class "Default")
      (node (ref "POTI") (pin "17") (pinfunction "17_17") (pintype "passive"))
      (node (ref "POTI") (pin "18") (pinfunction "18_18") (pintype "passive"))
      (node (ref "R12") (pin "2") (pinfunction "2_2") (pintype "passive"))
    )
    (net (code "18") (name "GAIN_MAX") (class "Default")
      (node (ref "POTI") (pin "15") (pinfunction "15_15") (pintype "passive"))
      (node (ref "POTI") (pin "16") (pinfunction "16_16") (pintype "passive"))
      (node (ref "R15") (pin "2") (pinfunction "2_2") (pintype "passive"))
    )
    (net (code "19") (name "GAIN_MIN") (class "Default")
      (node (ref "C11") (pin "2") (pinfunction "2_2") (pintype "passive"))
      (node (ref "C8") (pin "1") (pinfunction "1_1") (pintype "passive"))
      (node (ref "IC1") (pin "1") (pinfunction "OUT_1") (pintype "output"))
      (node (ref "POTI") (pin "19") (pinfunction "19_19") (pintype "passive"))
      (node (ref "POTI") (pin "20") (pinfunction "20_20") (pintype "passive"))
    )
    (net (code "20") (name "GND") (class "Default")
      (node (ref "C23") (pin "2") (pinfunction "2_2") (pintype "passive"))
      (node (ref "C24") (pin "2") (pinfunction "2_2") (pintype "passive"))
      (node (ref "C25") (pin "2") (pinfunction "2_2") (pintype "passive"))
      (node (ref "C52") (pin "2") (pinfunction "2_2") (pintype "passive"))
      (node (ref "C53") (pin "-") (pinfunction "-_-") (pintype "passive"))
      (node (ref "D14") (pin "2") (pinfunction "A_2") (pintype "passive"))
      (node (ref "IC9") (pin "2") (pinfunction "GND_2") (pintype "passive"))
      (node (ref "JP2") (pin "1") (pinfunction "1_1") (pintype "passive"))
      (node (ref "PROG") (pin "1") (pinfunction "1_1") (pintype "passive"))
      (node (ref "R39") (pin "2") (pinfunction "2_2") (pintype "passive"))
      (node (ref "R48") (pin "1") (pinfunction "1_1") (pintype "passive"))
      (node (ref "SJ6") (pin "2") (pinfunction "2_2") (pintype "passive"))
      (node (ref "TAP") (pin "15") (pinfunction "15_15") (pintype "passive"))
      (node (ref "TAP") (pin "16") (pinfunction "16_16") (pintype "passive"))
      (node (ref "TAP") (pin "17") (pinfunction "17_17") (pintype "passive"))
      (node (ref "TAP") (pin "18") (pinfunction "18_18") (pintype "passive"))
      (node (ref "TAP") (pin "19") (pinfunction "19_19") (pintype "passive"))
      (node (ref "TAP") (pin "20") (pinfunction "20_20") (pintype "passive"))
    )
    (net (code "21") (name "HP") (class "Default")
      (node (ref "IC3") (pin "13") (pinfunction "X1_13") (pintype "bidirectional"))
      (node (ref "MUSOR/NORMAL") (pin "1") (pinfunction "1_1") (pintype "passive"))
      (node (ref "POTI") (pin "11") (pinfunction "11_11") (pintype "passive"))
      (node (ref "POTI") (pin "12") (pinfunction "12_12") (pintype "passive"))
    )
    (net (code "22") (name "HPOUT") (class "Default")
      (node (ref "C61") (pin "2") (pinfunction "2_2") (pintype "passive"))
      (node (ref "IC11") (pin "22") (pinfunction "LOUT_22") (pintype "output"))
      (node (ref "L12") (pin "2") (pinfunction "2_2") (pintype "passive"))
    )
    (net (code "23") (name "IN+") (class "Default")
      (node (ref "C2") (pin "1") (pinfunction "1_1") (pintype "passive"))
      (node (ref "DSUB1") (pin "2") (pinfunction "M_2") (pintype "passive"))
      (node (ref "R2") (pin "2") (pinfunction "2_2") (pintype "passive"))
      (node (ref "RJ2") (pin "2") (pinfunction "2_2") (pintype "passive"))
    )
    (net (code "24") (name "IN-") (class "Default")
      (node (ref "C3") (pin "1") (pinfunction "1_1") (pintype "passive"))
      (node (ref "DSUB1") (pin "3") (pinfunction "M_3") (pintype "passive"))
      (node (ref "R3") (pin "2") (pinfunction "2_2") (pintype "passive"))
      (node (ref "RJ2") (pin "1") (pinfunction "1_1") (pintype "passive"))
    )
    (net (code "25") (name "LAMPA_CS") (class "Default")
      (node (ref "POTI") (pin "2") (pinfunction "2_2") (pintype "passive"))
      (node (ref "T2") (pin "1") (pinfunction "B_1") (pintype "passive"))
    )
    (net (code "26") (name "LAMPA_MAX") (class "Default")
      (node (ref "D17") (pin "C") (pinfunction "C_C") (pintype "passive"))
      (node (ref "POTI") (pin "3") (pinfunction "3_3") (pintype "passive"))
      (node (ref "R48") (pin "2") (pinfunction "2_2") (pintype "passive"))
    )
    (net (code "27") (name "LAMPA_MIN") (class "Default")
      (node (ref "POTI") (pin "1") (pinfunction "1_1") (pintype "passive"))
      (node (ref "R49") (pin "1") (pinfunction "1_1") (pintype "passive"))
    )
    (net (code "28") (name "MH") (class "Default")
      (node (ref "DIGIT") (pin "7") (pinfunction "7_7") (pintype "passive"))
      (node (ref "DIGIT") (pin "8") (pinfunction "8_8") (pintype "passive"))
      (node (ref "IC3") (pin "11") (pinfunction "A_11") (pintype "input"))
    )
    (net (code "29") (name "MIC_MUTE") (class "Default")
      (node (ref "D4") (pin "A") (pinfunction "A_A") (pintype "passive"))
      (node (ref "DIGIT") (pin "11") (pinfunction "11_11") (pintype "passive"))
      (node (ref "DIGIT") (pin "12") (pinfunction "12_12") (pintype "passive"))
    )
    (net (code "30") (name "MUTE") (class "Default")
      (node (ref "DIGIT") (pin "10") (pinfunction "10_10") (pintype "passive"))
      (node (ref "DIGIT") (pin "9") (pinfunction "9_9") (pintype "passive"))
      (node (ref "Q3") (pin "1") (pinfunction "G_1") (pintype "passive"))
    )
    (net (code "31") (name "N$49") (class "Default")
      (node (ref "IC3") (pin "14") (pinfunction "X_14") (pintype "bidirectional"))
      (node (ref "MUSOR/NORMAL") (pin "2") (pinfunction "2_2") (pintype "passive"))
      (node (ref "R30") (pin "2") (pinfunction "2_2") (pintype "passive"))
      (node (ref "SJ5") (pin "2") (pinfunction "2_2") (pintype "passive"))
    )
    (net (code "32") (name "N$50") (class "Default")
      (node (ref "IC3") (pin "15") (pinfunction "Y_15") (pintype "bidirectional"))
      (node (ref "R28") (pin "2") (pinfunction "2_2") (pintype "passive"))
      (node (ref "SJ4") (pin "2") (pinfunction "2_2") (pintype "passive"))
    )
    (net (code "33") (name "Net-(C1-Pad+)") (class "Default")
      (node (ref "C1") (pin "+") (pinfunction "+_+") (pintype "passive"))
      (node (ref "R1") (pin "1") (pinfunction "1_1") (pintype "passive"))
      (node (ref "R4") (pin "2") (pinfunction "2_2") (pintype "passive"))
    )
    (net (code "34") (name "Net-(C2-Pad2)") (class "Default")
      (node (ref "C2") (pin "2") (pinfunction "2_2") (pintype "passive"))
      (node (ref "R6") (pin "1") (pinfunction "1_1") (pintype "passive"))
    )
    (net (code "35") (name "Net-(C3-Pad2)") (class "Default")
      (node (ref "C3") (pin "2") (pinfunction "2_2") (pintype "passive"))
      (node (ref "R7") (pin "1") (pinfunction "1_1") (pintype "passive"))
    )
    (net (code "36") (name "Net-(C4-Pad2)") (class "Default")
      (node (ref "C4") (pin "2") (pinfunction "2_2") (pintype "passive"))
      (node (ref "R10") (pin "1") (pinfunction "1_1") (pintype "passive"))
    )
    (net (code "37") (name "Net-(C5-Pad2)") (class "Default")
      (node (ref "C5") (pin "2") (pinfunction "2_2") (pintype "passive"))
      (node (ref "R11") (pin "1") (pinfunction "1_1") (pintype "passive"))
      (node (ref "R8") (pin "2") (pinfunction "2_2") (pintype "passive"))
    )
    (net (code "38") (name "Net-(C6-Pad2)") (class "Default")
      (node (ref "C6") (pin "2") (pinfunction "2_2") (pintype "passive"))
      (node (ref "R8") (pin "1") (pinfunction "1_1") (pintype "passive"))
    )
    (net (code "39") (name "Net-(C11-Pad1)") (class "Default")
      (node (ref "C11") (pin "1") (pinfunction "1_1") (pintype "passive"))
      (node (ref "R16") (pin "2") (pinfunction "2_2") (pintype "passive"))
      (node (ref "R18") (pin "1") (pinfunction "1_1") (pintype "passive"))
    )
    (net (code "40") (name "Net-(C12-Pad1)") (class "Default")
      (node (ref "C12") (pin "1") (pinfunction "1_1") (pintype "passive"))
      (node (ref "R19") (pin "1") (pinfunction "1_1") (pintype "passive"))
    )
    (net (code "41") (name "Net-(C12-Pad2)") (class "Default")
      (node (ref "C12") (pin "2") (pinfunction "2_2") (pintype "passive"))
      (node (ref "D1") (pin "C") (pinfunction "C_C") (pintype "passive"))
      (node (ref "D2") (pin "A") (pinfunction "A_A") (pintype "passive"))
    )
    (net (code "42") (name "Net-(C13-Pad1)") (class "Default")
      (node (ref "C13") (pin "1") (pinfunction "1_1") (pintype "passive"))
      (node (ref "R17") (pin "2") (pinfunction "2_2") (pintype "passive"))
      (node (ref "R19") (pin "2") (pinfunction "2_2") (pintype "passive"))
    )
    (net (code "43") (name "Net-(C17-Pad1)") (class "Default")
      (node (ref "C17") (pin "1") (pinfunction "1_1") (pintype "passive"))
      (node (ref "D3") (pin "C") (pinfunction "C_C") (pintype "passive"))
      (node (ref "R27") (pin "2") (pinfunction "2_2") (pintype "passive"))
    )
    (net (code "44") (name "Net-(C20-Pad2)") (class "Default")
      (node (ref "C20") (pin "2") (pinfunction "2_2") (pintype "passive"))
      (node (ref "R34") (pin "1") (pinfunction "1_1") (pintype "passive"))
    )
    (net (code "45") (name "Net-(C21-Pad2)") (class "Default")
      (node (ref "C21") (pin "2") (pinfunction "2_2") (pintype "passive"))
      (node (ref "R35") (pin "1") (pinfunction "1_1") (pintype "passive"))
    )
    (net (code "46") (name "Net-(C54-Pad-)") (class "Default")
      (node (ref "C54") (pin "-") (pinfunction "-_-") (pintype "passive"))
      (node (ref "C55") (pin "2") (pinfunction "2_2") (pintype "passive"))
      (node (ref "D15") (pin "A") (pinfunction "A_A") (pintype "passive"))
      (node (ref "D19") (pin "A") (pinfunction "A_A") (pintype "passive"))
      (node (ref "SJ1") (pin "2") (pinfunction "2_2") (pintype "passive"))
      (node (ref "SJ7") (pin "1") (pinfunction "1_1") (pintype "passive"))
    )
    (net (code "47") (name "Net-(C63-Pad1)") (class "Default")
      (node (ref "C63") (pin "1") (pinfunction "1_1") (pintype "passive"))
      (node (ref "C65") (pin "+") (pinfunction "+_+") (pintype "passive"))
      (node (ref "L10") (pin "2") (pinfunction "2_2") (pintype "passive"))
      (node (ref "R52") (pin "2") (pinfunction "2_2") (pintype "passive"))
    )
    (net (code "48") (name "Net-(C64-Pad2)") (class "Default")
      (node (ref "C64") (pin "2") (pinfunction "2_2") (pintype "passive"))
      (node (ref "L11") (pin "2") (pinfunction "2_2") (pintype "passive"))
      (node (ref "L12") (pin "1") (pinfunction "1_1") (pintype "passive"))
      (node (ref "R53") (pin "1") (pinfunction "1_1") (pintype "passive"))
    )
    (net (code "49") (name "Net-(C66-Pad+)") (class "Default")
      (node (ref "C66") (pin "+") (pinfunction "+_+") (pintype "passive"))
      (node (ref "C70") (pin "2") (pinfunction "2_2") (pintype "passive"))
      (node (ref "L11") (pin "1") (pinfunction "1_1") (pintype "passive"))
    )
    (net (code "50") (name "Net-(C68-Pad1)") (class "Default")
      (node (ref "C68") (pin "1") (pinfunction "1_1") (pintype "passive"))
      (node (ref "SJ4") (pin "1") (pinfunction "1_1") (pintype "passive"))
    )
    (net (code "51") (name "Net-(C69-Pad1)") (class "Default")
      (node (ref "C69") (pin "1") (pinfunction "1_1") (pintype "passive"))
      (node (ref "SJ5") (pin "1") (pinfunction "1_1") (pintype "passive"))
    )
    (net (code "52") (name "Net-(C71-Pad1)") (class "Default")
      (node (ref "C71") (pin "1") (pinfunction "1_1") (pintype "passive"))
      (node (ref "R55") (pin "2") (pinfunction "2_2") (pintype "passive"))
      (node (ref "SD2") (pin "HACK") (pinfunction "HACK_HACK") (pintype "bidirectional"))
    )
    (net (code "53") (name "Net-(D3-PadA)") (class "Default")
      (node (ref "D3") (pin "A") (pinfunction "A_A") (pintype "passive"))
      (node (ref "R26") (pin "2") (pinfunction "2_2") (pintype "passive"))
    )
    (net (code "54") (name "Net-(D12-A)") (class "Default")
      (node (ref "D12") (pin "2") (pinfunction "A_2") (pintype "passive"))
      (node (ref "RJ2") (pin "8") (pinfunction "8_8") (pintype "passive"))
    )
    (net (code "55") (name "Net-(D13-A)") (class "Default")
      (node (ref "D13") (pin "2") (pinfunction "A_2") (pintype "passive"))
      (node (ref "DSUB1") (pin "8") (pinfunction "M_8") (pintype "passive"))
    )
    (net (code "56") (name "Net-(D14-C)") (class "Default")
      (node (ref "D14") (pin "1") (pinfunction "C_1") (pintype "passive"))
      (node (ref "JP1") (pin "1") (pinfunction "1_1") (pintype "passive"))
      (node (ref "L9") (pin "1") (pinfunction "1_1") (pintype "passive"))
    )
    (net (code "57") (name "Net-(D16-PadC)") (class "Default")
      (node (ref "D16") (pin "C") (pinfunction "C_C") (pintype "passive"))
      (node (ref "D17") (pin "A") (pinfunction "A_A") (pintype "passive"))
    )
    (net (code "58") (name "Net-(D18-PadA)") (class "Default")
      (node (ref "D18") (pin "A") (pinfunction "A_A") (pintype "passive"))
      (node (ref "D19") (pin "C") (pinfunction "C_C") (pintype "passive"))
      (node (ref "R55") (pin "1") (pinfunction "1_1") (pintype "passive"))
    )
    (net (code "59") (name "Net-(F2-Pad2)") (class "Default")
      (node (ref "F2") (pin "2") (pinfunction "2_2") (pintype "passive"))
      (node (ref "L7") (pin "1") (pinfunction "1_1") (pintype "passive"))
    )
    (net (code "60") (name "Net-(F_LED-Pad2)") (class "Default")
      (node (ref "F_LED") (pin "2") (pinfunction "2_2") (pintype "passive"))
      (node (ref "R27") (pin "1") (pinfunction "1_1") (pintype "passive"))
    )
    (net (code "61") (name "Net-(HP_KIB-S)") (class "Default")
      (node (ref "C66") (pin "-") (pinfunction "-_-") (pintype "passive"))
      (node (ref "HP_KI") (pin "2") (pinfunction "S_2") (pintype "passive"))
      (node (ref "R56") (pin "1") (pinfunction "1_1") (pintype "passive"))
    )
    (net (code "62") (name "Net-(IC1A-+IN)") (class "Default")
      (node (ref "C10") (pin "1") (pinfunction "1_1") (pintype "passive"))
      (node (ref "IC1") (pin "3") (pinfunction "+IN_3") (pintype "input"))
      (node (ref "R10") (pin "2") (pinfunction "2_2") (pintype "passive"))
      (node (ref "R14") (pin "2") (pinfunction "2_2") (pintype "passive"))
    )
    (net (code "63") (name "Net-(IC1A--IN)") (class "Default")
      (node (ref "C6") (pin "1") (pinfunction "1_1") (pintype "passive"))
      (node (ref "C8") (pin "2") (pinfunction "2_2") (pintype "passive"))
      (node (ref "IC1") (pin "2") (pinfunction "-IN_2") (pintype "input"))
      (node (ref "R11") (pin "2") (pinfunction "2_2") (pintype "passive"))
      (node (ref "R12") (pin "1") (pinfunction "1_1") (pintype "passive"))
    )
    (net (code "64") (name "Net-(IC1B-+IN)") (class "Default")
      (node (ref "FENYELL") (pin "2") (pinfunction "2_2") (pintype "passive"))
      (node (ref "IC1") (pin "5") (pinfunction "+IN_5") (pintype "input"))
      (node (ref "Q1") (pin "3") (pinfunction "D_3") (pintype "passive"))
      (node (ref "R18") (pin "2") (pinfunction "2_2") (pintype "passive"))
    )
    (net (code "65") (name "Net-(IC1B--IN)") (class "Default")
      (node (ref "C14") (pin "2") (pinfunction "2_2") (pintype "passive"))
      (node (ref "IC1") (pin "6") (pinfunction "-IN_6") (pintype "input"))
      (node (ref "R20") (pin "2") (pinfunction "2_2") (pintype "passive"))
      (node (ref "R21") (pin "1") (pinfunction "1_1") (pintype "passive"))
    )
    (net (code "66") (name "Net-(IC1B-OUT)") (class "Default")
      (node (ref "C14") (pin "1") (pinfunction "1_1") (pintype "passive"))
      (node (ref "C15") (pin "2") (pinfunction "2_2") (pintype "passive"))
      (node (ref "IC1") (pin "7") (pinfunction "OUT_7") (pintype "output"))
      (node (ref "IC2") (pin "3") (pinfunction "+IN_3") (pintype "input"))
      (node (ref "R21") (pin "2") (pinfunction "2_2") (pintype "passive"))
    )
    (net (code "67") (name "Net-(IC2A--IN)") (class "Default")
      (node (ref "C16") (pin "2") (pinfunction "2_2") (pintype "passive"))
      (node (ref "IC2") (pin "2") (pinfunction "-IN_2") (pintype "input"))
      (node (ref "R22") (pin "2") (pinfunction "2_2") (pintype "passive"))
      (node (ref "R23") (pin "1") (pinfunction "1_1") (pintype "passive"))
    )
    (net (code "68") (name "Net-(IC2A-OUT)") (class "Default")
      (node (ref "C16") (pin "1") (pinfunction "1_1") (pintype "passive"))
      (node (ref "IC2") (pin "1") (pinfunction "OUT_1") (pintype "output"))
      (node (ref "LED1") (pin "K") (pinfunction "C_K") (pintype "passive"))
      (node (ref "R25") (pin "2") (pinfunction "2_2") (pintype "passive"))
      (node (ref "R26") (pin "1") (pinfunction "1_1") (pintype "passive"))
    )
    (net (code "69") (name "Net-(IC2B-+IN)") (class "Default")
      (node (ref "C7") (pin "1") (pinfunction "1_1") (pintype "passive"))
      (node (ref "IC2") (pin "5") (pinfunction "+IN_5") (pintype "input"))
      (node (ref "R6") (pin "2") (pinfunction "2_2") (pintype "passive"))
      (node (ref "R9") (pin "2") (pinfunction "2_2") (pintype "passive"))
    )
    (net (code "70") (name "Net-(IC2B--IN)") (class "Default")
      (node (ref "C9") (pin "2") (pinfunction "2_2") (pintype "passive"))
      (node (ref "IC2") (pin "6") (pinfunction "-IN_6") (pintype "input"))
      (node (ref "R13") (pin "1") (pinfunction "1_1") (pintype "passive"))
      (node (ref "R7") (pin "2") (pinfunction "2_2") (pintype "passive"))
    )
    (net (code "71") (name "Net-(IC2B-OUT)") (class "Default")
      (node (ref "C9") (pin "1") (pinfunction "1_1") (pintype "passive"))
      (node (ref "IC2") (pin "7") (pinfunction "OUT_7") (pintype "output"))
      (node (ref "R13") (pin "2") (pinfunction "2_2") (pintype "passive"))
      (node (ref "R17") (pin "1") (pinfunction "1_1") (pintype "passive"))
    )
    (net (code "72") (name "Net-(IC3A-INH)") (class "Default")
      (node (ref "IC3") (pin "6") (pinfunction "INH_6") (pintype "input"))
      (node (ref "Q3") (pin "3") (pinfunction "D_3") (pintype "passive"))
      (node (ref "R54") (pin "1") (pinfunction "1_1") (pintype "passive"))
    )
    (net (code "73") (name "Net-(IC3A-Y0)") (class "Default")
      (node (ref "IC3") (pin "2") (pinfunction "Y0_2") (pintype "bidirectional"))
      (node (ref "IC3") (pin "4") (pinfunction "Z_4") (pintype "bidirectional"))
    )
    (net (code "74") (name "Net-(IC4A-+IN)") (class "Default")
      (node (ref "C15") (pin "1") (pinfunction "1_1") (pintype "passive"))
      (node (ref "IC4") (pin "3") (pinfunction "+IN_3") (pintype "input"))
      (node (ref "R24") (pin "2") (pinfunction "2_2") (pintype "passive"))
      (node (ref "R29") (pin "2") (pinfunction "2_2") (pintype "passive"))
    )
    (net (code "75") (name "Net-(IC4A--IN)") (class "Default")
      (node (ref "C18") (pin "2") (pinfunction "2_2") (pintype "passive"))
      (node (ref "IC4") (pin "2") (pinfunction "-IN_2") (pintype "input"))
      (node (ref "R31") (pin "2") (pinfunction "2_2") (pintype "passive"))
      (node (ref "R32") (pin "1") (pinfunction "1_1") (pintype "passive"))
    )
    (net (code "76") (name "Net-(IC4A-OUT)") (class "Default")
      (node (ref "C18") (pin "1") (pinfunction "1_1") (pintype "passive"))
      (node (ref "C20") (pin "1") (pinfunction "1_1") (pintype "passive"))
      (node (ref "IC4") (pin "1") (pinfunction "OUT_1") (pintype "output"))
      (node (ref "R32") (pin "2") (pinfunction "2_2") (pintype "passive"))
    )
    (net (code "77") (name "Net-(IC4B--IN)") (class "Default")
      (node (ref "C19") (pin "2") (pinfunction "2_2") (pintype "passive"))
      (node (ref "IC4") (pin "6") (pinfunction "-IN_6") (pintype "input"))
      (node (ref "R29") (pin "1") (pinfunction "1_1") (pintype "passive"))
      (node (ref "R33") (pin "1") (pinfunction "1_1") (pintype "passive"))
    )
    (net (code "78") (name "Net-(IC4B-OUT)") (class "Default")
      (node (ref "C19") (pin "1") (pinfunction "1_1") (pintype "passive"))
      (node (ref "C21") (pin "1") (pinfunction "1_1") (pintype "passive"))
      (node (ref "IC4") (pin "7") (pinfunction "OUT_7") (pintype "output"))
      (node (ref "R33") (pin "2") (pinfunction "2_2") (pintype "passive"))
    )
    (net (code "79") (name "Net-(IC11-BSL)") (class "Default")
      (node (ref "C61") (pin "1") (pinfunction "1_1") (pintype "passive"))
      (node (ref "IC11") (pin "21") (pinfunction "BSL_21") (pintype "passive"))
    )
    (net (code "80") (name "Net-(IC11-BSR)") (class "Default")
      (node (ref "C60") (pin "1") (pinfunction "1_1") (pintype "passive"))
      (node (ref "IC11") (pin "16") (pinfunction "BSR_16") (pintype "passive"))
    )
    (net (code "81") (name "Net-(IC11-BYPASS)") (class "Default")
      (node (ref "C56") (pin "1") (pinfunction "1_1") (pintype "passive"))
      (node (ref "IC11") (pin "7") (pinfunction "BYPASS_7") (pintype "input"))
    )
    (net (code "82") (name "Net-(IC11-GAIN0)") (class "Default")
      (node (ref "IC11") (pin "18") (pinfunction "GAIN0_18") (pintype "input"))
      (node (ref "SJ2") (pin "2") (pinfunction "2_2") (pintype "passive"))
    )
    (net (code "83") (name "Net-(IC11-LIN)") (class "Default")
      (node (ref "C69") (pin "2") (pinfunction "2_2") (pintype "passive"))
      (node (ref "IC11") (pin "5") (pinfunction "LIN_5") (pintype "input"))
    )
    (net (code "84") (name "Net-(IC11-MUTE)") (class "Default")
      (node (ref "IC11") (pin "4") (pinfunction "MUTE_4") (pintype "input"))
      (node (ref "SJ8") (pin "1") (pinfunction "1_1") (pintype "passive"))
    )
    (net (code "85") (name "Net-(IC11-RIN)") (class "Default")
      (node (ref "C68") (pin "2") (pinfunction "2_2") (pintype "passive"))
      (node (ref "IC11") (pin "6") (pinfunction "RIN_6") (pintype "input"))
    )
    (net (code "86") (name "Net-(IC11-VCLAMP)") (class "Default")
      (node (ref "C59") (pin "1") (pinfunction "1_1") (pintype "passive"))
      (node (ref "IC11") (pin "11") (pinfunction "VCLAMP_11") (pintype "input"))
    )
    (net (code "87") (name "Net-(LAMPAB-S)") (class "Default")
      (node (ref "LAMPA") (pin "2") (pinfunction "S_2") (pintype "passive"))
      (node (ref "T2") (pin "2") (pinfunction "C_2") (pintype "passive"))
    )
    (net (code "88") (name "Net-(LED1-PadA)") (class "Default")
      (node (ref "LED1") (pin "A") (pinfunction "A_A") (pintype "passive"))
      (node (ref "R23") (pin "2") (pinfunction "2_2") (pintype "passive"))
      (node (ref "R25") (pin "1") (pinfunction "1_1") (pintype "passive"))
    )
    (net (code "89") (name "Net-(PROG-Pad4)") (class "Default")
      (node (ref "PROG") (pin "4") (pinfunction "4_4") (pintype "passive"))
      (node (ref "R36") (pin "2") (pinfunction "2_2") (pintype "passive"))
    )
    (net (code "90") (name "Net-(PROG-Pad8)") (class "Default")
      (node (ref "PROG") (pin "8") (pinfunction "8_8") (pintype "passive"))
      (node (ref "R37") (pin "2") (pinfunction "2_2") (pintype "passive"))
    )
    (net (code "91") (name "Net-(Q1-G)") (class "Default")
      (node (ref "D4") (pin "C") (pinfunction "C_C") (pintype "passive"))
      (node (ref "Q1") (pin "1") (pinfunction "G_1") (pintype "passive"))
      (node (ref "R38") (pin "2") (pinfunction "2_2") (pintype "passive"))
    )
    (net (code "92") (name "Net-(SD2-CTRL)") (class "Default")
      (node (ref "C48") (pin "1") (pinfunction "1_1") (pintype "passive"))
      (node (ref "C49") (pin "+") (pinfunction "+_+") (pintype "passive"))
      (node (ref "R47") (pin "2") (pinfunction "2_2") (pintype "passive"))
      (node (ref "SD2") (pin "CONTROL") (pinfunction "CTRL_CONTROL") (pintype "bidirectional"))
    )
    (net (code "93") (name "Net-(SD2-IN+)") (class "Default")
      (node (ref "C22") (pin "+") (pinfunction "+_+") (pintype "passive"))
      (node (ref "C47") (pin "+") (pinfunction "+_+") (pintype "passive"))
      (node (ref "L7") (pin "2") (pinfunction "2_2") (pintype "passive"))
      (node (ref "SD2") (pin "INPUT+") (pinfunction "IN+_INPUT+") (pintype "bidirectional"))
    )
    (net (code "94") (name "Net-(SD2-IN-)") (class "Default")
      (node (ref "C22") (pin "-") (pinfunction "-_-") (pintype "passive"))
      (node (ref "C47") (pin "-") (pinfunction "-_-") (pintype "passive"))
      (node (ref "C48") (pin "2") (pinfunction "2_2") (pintype "passive"))
      (node (ref "C49") (pin "-") (pinfunction "-_-") (pintype "passive"))
      (node (ref "L8") (pin "2") (pinfunction "2_2") (pintype "passive"))
      (node (ref "R47") (pin "1") (pinfunction "1_1") (pintype "passive"))
      (node (ref "SD2") (pin "INPUT-") (pinfunction "IN-_INPUT-") (pintype "bidirectional"))
    )
    (net (code "95") (name "Net-(SD2-PadOUT-)") (class "Default")
      (node (ref "SD2") (pin "OUT-") (pinfunction "OUT-_OUT-") (pintype "bidirectional"))
      (node (ref "SJ7") (pin "2") (pinfunction "2_2") (pintype "passive"))
    )
    (net (code "96") (name "Net-(SP_KIB-S)") (class "Default")
      (node (ref "C65") (pin "-") (pinfunction "-_-") (pintype "passive"))
      (node (ref "SP_KI") (pin "2") (pinfunction "S_2") (pintype "passive"))
    )
    (net (code "97") (name "Net-(T2-E)") (class "Default")
      (node (ref "R50") (pin "1") (pinfunction "1_1") (pintype "passive"))
      (node (ref "T2") (pin "3") (pinfunction "E_3") (pintype "passive"))
    )
    (net (code "98") (name "OUT+") (class "Default")
      (node (ref "DSUB1") (pin "4") (pinfunction "M_4") (pintype "passive"))
      (node (ref "R34") (pin "2") (pinfunction "2_2") (pintype "passive"))
      (node (ref "RJ2") (pin "6") (pinfunction "6_6") (pintype "passive"))
    )
    (net (code "99") (name "OUT-") (class "Default")
      (node (ref "DSUB1") (pin "5") (pinfunction "M_5") (pintype "passive"))
      (node (ref "R35") (pin "2") (pinfunction "2_2") (pintype "passive"))
      (node (ref "RJ2") (pin "3") (pinfunction "3_3") (pintype "passive"))
    )
    (net (code "100") (name "POTI_JEL") (class "Default")
      (node (ref "C13") (pin "2") (pinfunction "2_2") (pintype "passive"))
      (node (ref "POTI") (pin "7") (pinfunction "7_7") (pintype "passive"))
      (node (ref "POTI") (pin "8") (pinfunction "8_8") (pintype "passive"))
    )
    (net (code "101") (name "SP") (class "Default")
      (node (ref "MUSOR/NORMAL") (pin "5") (pinfunction "5_5") (pintype "passive"))
      (node (ref "POTI") (pin "10") (pinfunction "10_10") (pintype "passive"))
      (node (ref "POTI") (pin "9") (pinfunction "9_9") (pintype "passive"))
    )
    (net (code "102") (name "SPM") (class "Default")
      (node (ref "DIGIT") (pin "5") (pinfunction "5_5") (pintype "passive"))
      (node (ref "DIGIT") (pin "6") (pinfunction "6_6") (pintype "passive"))
      (node (ref "IC3") (pin "10") (pinfunction "B_10") (pintype "input"))
    )
    (net (code "103") (name "SPOUT") (class "Default")
      (node (ref "C60") (pin "2") (pinfunction "2_2") (pintype "passive"))
      (node (ref "C71") (pin "2") (pinfunction "2_2") (pintype "passive"))
      (node (ref "IC11") (pin "15") (pinfunction "ROUT_15") (pintype "output"))
      (node (ref "L10") (pin "1") (pinfunction "1_1") (pintype "passive"))
    )
    (net (code "104") (name "VDD") (class "Default")
      (node (ref "C26") (pin "1") (pinfunction "1_1") (pintype "passive"))
      (node (ref "C57") (pin "+") (pinfunction "+_+") (pintype "passive"))
      (node (ref "C58") (pin "1") (pinfunction "1_1") (pintype "passive"))
      (node (ref "IC1") (pin "8") (pinfunction "V+_8") (pintype "power_in"))
      (node (ref "IC11") (pin "19") (pinfunction "AVCC_19") (pintype "input"))
      (node (ref "IC11") (pin "20") (pinfunction "AVCC_20") (pintype "input"))
      (node (ref "IC2") (pin "8") (pinfunction "V+_8") (pintype "power_in"))
      (node (ref "IC4") (pin "8") (pinfunction "V+_8") (pintype "power_in"))
      (node (ref "R1") (pin "2") (pinfunction "2_2") (pintype "passive"))
      (node (ref "R51") (pin "1") (pinfunction "1_1") (pintype "passive"))
      (node (ref "SJ2") (pin "1") (pinfunction "1_1") (pintype "passive"))
    )
    (net (code "105") (name "VSS") (class "Default")
      (node (ref "C27") (pin "2") (pinfunction "2_2") (pintype "passive"))
      (node (ref "IC1") (pin "4") (pinfunction "V-_4") (pintype "power_in"))
      (node (ref "IC2") (pin "4") (pinfunction "V-_4") (pintype "power_in"))
      (node (ref "IC3") (pin "7") (pinfunction "VEE_7") (pintype "power_in"))
      (node (ref "IC4") (pin "4") (pinfunction "V-_4") (pintype "power_in"))
      (node (ref "SJ1") (pin "1") (pinfunction "1_1") (pintype "passive"))
    )
    (net (code "106") (name "X0") (class "Default")
      (node (ref "IC3") (pin "12") (pinfunction "X0_12") (pintype "bidirectional"))
      (node (ref "MUSOR/NORMAL") (pin "3") (pinfunction "3_3") (pintype "passive"))
    )
    (net (code "107") (name "unconnected-(IC12-GND-Pad2)") (class "Default")
      (node (ref "IC12") (pin "2") (pinfunction "GND_2") (pintype "passive"))
    )
    (net (code "108") (name "unconnected-(IC12-VI-Pad1)") (class "Default")
      (node (ref "IC12") (pin "1") (pinfunction "VI_1") (pintype "input"))
    )
    (net (code "109") (name "unconnected-(IC12-VO-Pad3)") (class "Default")
      (node (ref "IC12") (pin "3") (pinfunction "VO_3") (pintype "passive"))
    )
    (net (code "110") (name "unconnected-(POTI-Pad4)") (class "Default")
      (node (ref "POTI") (pin "4") (pinfunction "4_4") (pintype "passive"))
    )
    (net (code "111") (name "unconnected-(SD2-PadSZAB)") (class "Default")
      (node (ref "SD2") (pin "SZAB") (pinfunction "SZAB_SZAB") (pintype "bidirectional"))
    )
    (net (code "112") (name "~{MCLR}") (class "Default")
      (node (ref "PROG") (pin "5") (pinfunction "5_5") (pintype "passive"))
      (node (ref "TAP") (pin "1") (pinfunction "1_1") (pintype "passive"))
      (node (ref "TAP") (pin "2") (pinfunction "2_2") (pintype "passive"))
    )
  )
)
